# Schematics.net
KiCad netlist of a schematic drawn in Altium Designer
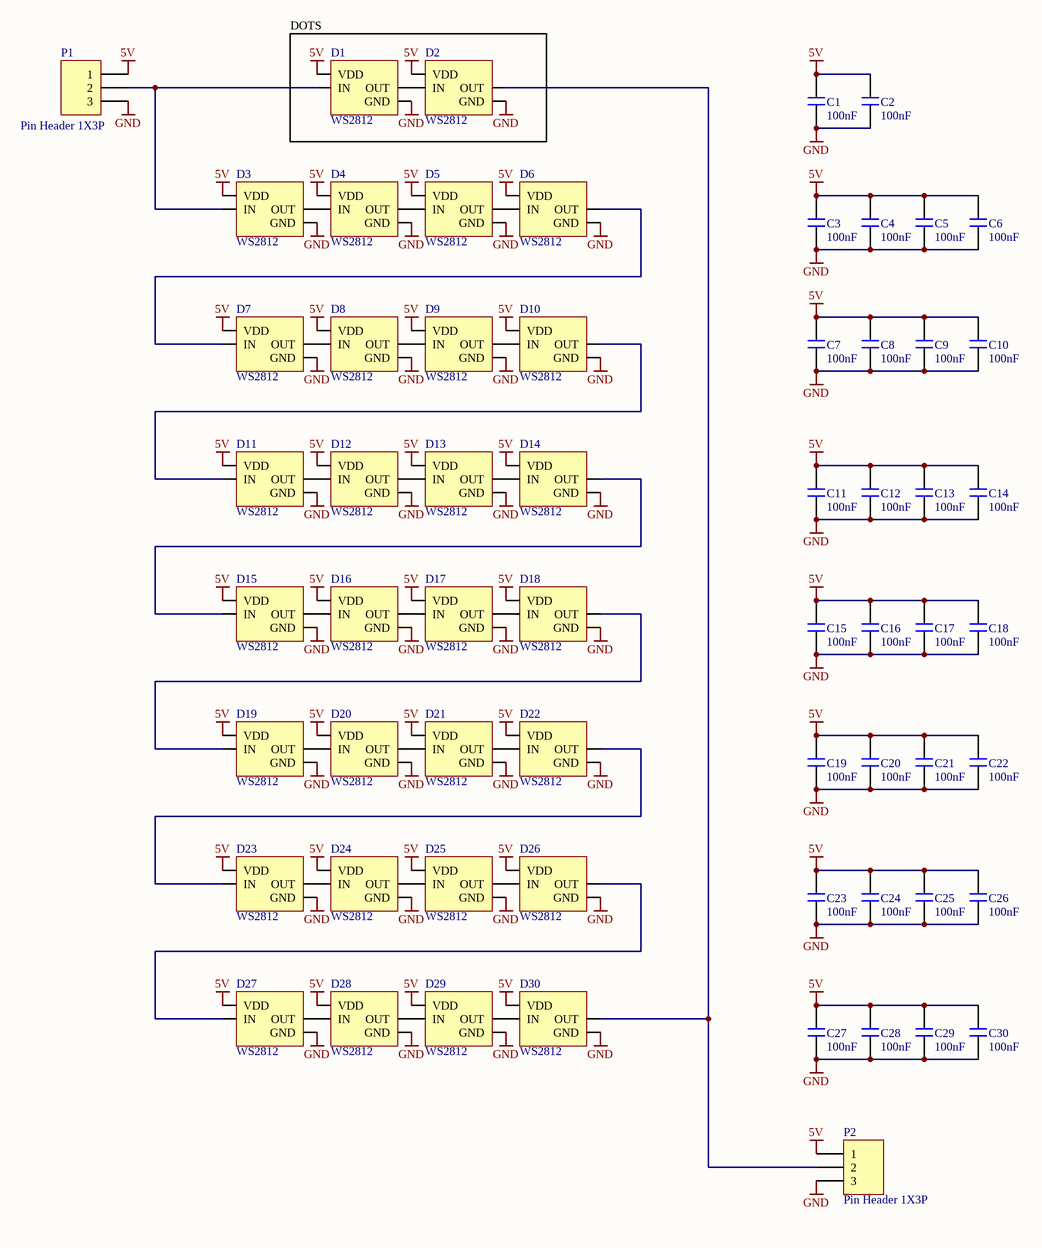
[diagram p0: Schematics.SchDoc]

(export (version "E")
  (design (tool "Eeschema 10.0.6"))
  (components
    (comp (ref "C1")
      (value "100nF")
      (footprint "EM-0805-C T1,25_SMD")
      (description "Capacitor")
      (fields (field (name "TOLERANCE") "+-5%"))
      (libsource (lib "Schematic") (part "Capacitor"))
    )
    (comp (ref "C2")
      (value "100nF")
      (footprint "EM-0805-C T1,25_SMD")
      (description "Capacitor")
      (fields (field (name "TOLERANCE") "+-5%"))
      (libsource (lib "Schematic") (part "Capacitor"))
    )
    (comp (ref "C3")
      (value "100nF")
      (footprint "EM-0805-C T1,25_SMD")
      (description "Capacitor")
      (fields (field (name "TOLERANCE") "+-5%"))
      (libsource (lib "Schematic") (part "Capacitor"))
    )
    (comp (ref "C4")
      (value "100nF")
      (footprint "EM-0805-C T1,25_SMD")
      (description "Capacitor")
      (fields (field (name "TOLERANCE") "+-5%"))
      (libsource (lib "Schematic") (part "Capacitor"))
    )
    (comp (ref "C5")
      (value "100nF")
      (footprint "EM-0805-C T1,25_SMD")
      (description "Capacitor")
      (fields (field (name "TOLERANCE") "+-5%"))
      (libsource (lib "Schematic") (part "Capacitor"))
    )
    (comp (ref "C6")
      (value "100nF")
      (footprint "EM-0805-C T1,25_SMD")
      (description "Capacitor")
      (fields (field (name "TOLERANCE") "+-5%"))
      (libsource (lib "Schematic") (part "Capacitor"))
    )
    (comp (ref "C7")
      (value "100nF")
      (footprint "EM-0805-C T1,25_SMD")
      (description "Capacitor")
      (fields (field (name "TOLERANCE") "+-5%"))
      (libsource (lib "Schematic") (part "Capacitor"))
    )
    (comp (ref "C8")
      (value "100nF")
      (footprint "EM-0805-C T1,25_SMD")
      (description "Capacitor")
      (fields (field (name "TOLERANCE") "+-5%"))
      (libsource (lib "Schematic") (part "Capacitor"))
    )
    (comp (ref "C9")
      (value "100nF")
      (footprint "EM-0805-C T1,25_SMD")
      (description "Capacitor")
      (fields (field (name "TOLERANCE") "+-5%"))
      (libsource (lib "Schematic") (part "Capacitor"))
    )
    (comp (ref "C10")
      (value "100nF")
      (footprint "EM-0805-C T1,25_SMD")
      (description "Capacitor")
      (fields (field (name "TOLERANCE") "+-5%"))
      (libsource (lib "Schematic") (part "Capacitor"))
    )
    (comp (ref "C11")
      (value "100nF")
      (footprint "EM-0805-C T1,25_SMD")
      (description "Capacitor")
      (fields (field (name "TOLERANCE") "+-5%"))
      (libsource (lib "Schematic") (part "Capacitor"))
    )
    (comp (ref "C12")
      (value "100nF")
      (footprint "EM-0805-C T1,25_SMD")
      (description "Capacitor")
      (fields (field (name "TOLERANCE") "+-5%"))
      (libsource (lib "Schematic") (part "Capacitor"))
    )
    (comp (ref "C13")
      (value "100nF")
      (footprint "EM-0805-C T1,25_SMD")
      (description "Capacitor")
      (fields (field (name "TOLERANCE") "+-5%"))
      (libsource (lib "Schematic") (part "Capacitor"))
    )
    (comp (ref "C14")
      (value "100nF")
      (footprint "EM-0805-C T1,25_SMD")
      (description "Capacitor")
      (fields (field (name "TOLERANCE") "+-5%"))
      (libsource (lib "Schematic") (part "Capacitor"))
    )
    (comp (ref "C15")
      (value "100nF")
      (footprint "EM-0805-C T1,25_SMD")
      (description "Capacitor")
      (fields (field (name "TOLERANCE") "+-5%"))
      (libsource (lib "Schematic") (part "Capacitor"))
    )
    (comp (ref "C16")
      (value "100nF")
      (footprint "EM-0805-C T1,25_SMD")
      (description "Capacitor")
      (fields (field (name "TOLERANCE") "+-5%"))
      (libsource (lib "Schematic") (part "Capacitor"))
    )
    (comp (ref "C17")
      (value "100nF")
      (footprint "EM-0805-C T1,25_SMD")
      (description "Capacitor")
      (fields (field (name "TOLERANCE") "+-5%"))
      (libsource (lib "Schematic") (part "Capacitor"))
    )
    (comp (ref "C18")
      (value "100nF")
      (footprint "EM-0805-C T1,25_SMD")
      (description "Capacitor")
      (fields (field (name "TOLERANCE") "+-5%"))
      (libsource (lib "Schematic") (part "Capacitor"))
    )
    (comp (ref "C19")
      (value "100nF")
      (footprint "EM-0805-C T1,25_SMD")
      (description "Capacitor")
      (fields (field (name "TOLERANCE") "+-5%"))
      (libsource (lib "Schematic") (part "Capacitor"))
    )
    (comp (ref "C20")
      (value "100nF")
      (footprint "EM-0805-C T1,25_SMD")
      (description "Capacitor")
      (fields (field (name "TOLERANCE") "+-5%"))
      (libsource (lib "Schematic") (part "Capacitor"))
    )
    (comp (ref "C21")
      (value "100nF")
      (footprint "EM-0805-C T1,25_SMD")
      (description "Capacitor")
      (fields (field (name "TOLERANCE") "+-5%"))
      (libsource (lib "Schematic") (part "Capacitor"))
    )
    (comp (ref "C22")
      (value "100nF")
      (footprint "EM-0805-C T1,25_SMD")
      (description "Capacitor")
      (fields (field (name "TOLERANCE") "+-5%"))
      (libsource (lib "Schematic") (part "Capacitor"))
    )
    (comp (ref "C23")
      (value "100nF")
      (footprint "EM-0805-C T1,25_SMD")
      (description "Capacitor")
      (fields (field (name "TOLERANCE") "+-5%"))
      (libsource (lib "Schematic") (part "Capacitor"))
    )
    (comp (ref "C24")
      (value "100nF")
      (footprint "EM-0805-C T1,25_SMD")
      (description "Capacitor")
      (fields (field (name "TOLERANCE") "+-5%"))
      (libsource (lib "Schematic") (part "Capacitor"))
    )
    (comp (ref "C25")
      (value "100nF")
      (footprint "EM-0805-C T1,25_SMD")
      (description "Capacitor")
      (fields (field (name "TOLERANCE") "+-5%"))
      (libsource (lib "Schematic") (part "Capacitor"))
    )
    (comp (ref "C26")
      (value "100nF")
      (footprint "EM-0805-C T1,25_SMD")
      (description "Capacitor")
      (fields (field (name "TOLERANCE") "+-5%"))
      (libsource (lib "Schematic") (part "Capacitor"))
    )
    (comp (ref "C27")
      (value "100nF")
      (footprint "EM-0805-C T1,25_SMD")
      (description "Capacitor")
      (fields (field (name "TOLERANCE") "+-5%"))
      (libsource (lib "Schematic") (part "Capacitor"))
    )
    (comp (ref "C28")
      (value "100nF")
      (footprint "EM-0805-C T1,25_SMD")
      (description "Capacitor")
      (fields (field (name "TOLERANCE") "+-5%"))
      (libsource (lib "Schematic") (part "Capacitor"))
    )
    (comp (ref "C29")
      (value "100nF")
      (footprint "EM-0805-C T1,25_SMD")
      (description "Capacitor")
      (fields (field (name "TOLERANCE") "+-5%"))
      (libsource (lib "Schematic") (part "Capacitor"))
    )
    (comp (ref "C30")
      (value "100nF")
      (footprint "EM-0805-C T1,25_SMD")
      (description "Capacitor")
      (fields (field (name "TOLERANCE") "+-5%"))
      (libsource (lib "Schematic") (part "Capacitor"))
    )
    (comp (ref "D1") (value "WS2812") (footprint "WS2812B") (libsource (lib "Schematic") (part "WS2812")))
    (comp (ref "D2") (value "WS2812") (footprint "WS2812B") (libsource (lib "Schematic") (part "WS2812")))
    (comp (ref "D3") (value "WS2812") (footprint "WS2812B") (libsource (lib "Schematic") (part "WS2812")))
    (comp (ref "D4") (value "WS2812") (footprint "WS2812B") (libsource (lib "Schematic") (part "WS2812")))
    (comp (ref "D5") (value "WS2812") (footprint "WS2812B") (libsource (lib "Schematic") (part "WS2812")))
    (comp (ref "D6") (value "WS2812") (footprint "WS2812B") (libsource (lib "Schematic") (part "WS2812")))
    (comp (ref "D7") (value "WS2812") (footprint "WS2812B") (libsource (lib "Schematic") (part "WS2812")))
    (comp (ref "D8") (value "WS2812") (footprint "WS2812B") (libsource (lib "Schematic") (part "WS2812")))
    (comp (ref "D9") (value "WS2812") (footprint "WS2812B") (libsource (lib "Schematic") (part "WS2812")))
    (comp (ref "D10") (value "WS2812") (footprint "WS2812B") (libsource (lib "Schematic") (part "WS2812")))
    (comp (ref "D11") (value "WS2812") (footprint "WS2812B") (libsource (lib "Schematic") (part "WS2812")))
    (comp (ref "D12") (value "WS2812") (footprint "WS2812B") (libsource (lib "Schematic") (part "WS2812")))
    (comp (ref "D13") (value "WS2812") (footprint "WS2812B") (libsource (lib "Schematic") (part "WS2812")))
    (comp (ref "D14") (value "WS2812") (footprint "WS2812B") (libsource (lib "Schematic") (part "WS2812")))
    (comp (ref "D15") (value "WS2812") (footprint "WS2812B") (libsource (lib "Schematic") (part "WS2812")))
    (comp (ref "D16") (value "WS2812") (footprint "WS2812B") (libsource (lib "Schematic") (part "WS2812")))
    (comp (ref "D17") (value "WS2812") (footprint "WS2812B") (libsource (lib "Schematic") (part "WS2812")))
    (comp (ref "D18") (value "WS2812") (footprint "WS2812B") (libsource (lib "Schematic") (part "WS2812")))
    (comp (ref "D19") (value "WS2812") (footprint "WS2812B") (libsource (lib "Schematic") (part "WS2812")))
    (comp (ref "D20") (value "WS2812") (footprint "WS2812B") (libsource (lib "Schematic") (part "WS2812")))
    (comp (ref "D21") (value "WS2812") (footprint "WS2812B") (libsource (lib "Schematic") (part "WS2812")))
    (comp (ref "D22") (value "WS2812") (footprint "WS2812B") (libsource (lib "Schematic") (part "WS2812")))
    (comp (ref "D23") (value "WS2812") (footprint "WS2812B") (libsource (lib "Schematic") (part "WS2812")))
    (comp (ref "D24") (value "WS2812") (footprint "WS2812B") (libsource (lib "Schematic") (part "WS2812")))
    (comp (ref "D25") (value "WS2812") (footprint "WS2812B") (libsource (lib "Schematic") (part "WS2812")))
    (comp (ref "D26") (value "WS2812") (footprint "WS2812B") (libsource (lib "Schematic") (part "WS2812")))
    (comp (ref "D27") (value "WS2812") (footprint "WS2812B") (libsource (lib "Schematic") (part "WS2812")))
    (comp (ref "D28") (value "WS2812") (footprint "WS2812B") (libsource (lib "Schematic") (part "WS2812")))
    (comp (ref "D29") (value "WS2812") (footprint "WS2812B") (libsource (lib "Schematic") (part "WS2812")))
    (comp (ref "D30") (value "WS2812") (footprint "WS2812B") (libsource (lib "Schematic") (part "WS2812")))
    (comp (ref "P1")
      (value "Pin Header 1X3P")
      (footprint "CON Header 1X3")
      (description "Header 3-Pin")
      (libsource (lib "Schematic") (part "Pin Header 3"))
    )
    (comp (ref "P2")
      (value "Pin Header 1X3P")
      (footprint "CON Header 1X3")
      (description "Header 3-Pin")
      (libsource (lib "") (part "Pin Header 3_1"))
    )
  )
  (nets
    (net (code "1") (name "5V") (class "Default")
      (node (ref "C1") (pin "2") (pinfunction "2_2") (pintype "passive"))
      (node (ref "C10") (pin "2") (pinfunction "2_2") (pintype "passive"))
      (node (ref "C11") (pin "2") (pinfunction "2_2") (pintype "passive"))
      (node (ref "C12") (pin "2") (pinfunction "2_2") (pintype "passive"))
      (node (ref "C13") (pin "2") (pinfunction "2_2") (pintype "passive"))
      (node (ref "C14") (pin "2") (pinfunction "2_2") (pintype "passive"))
      (node (ref "C15") (pin "2") (pinfunction "2_2") (pintype "passive"))
      (node (ref "C16") (pin "2") (pinfunction "2_2") (pintype "passive"))
      (node (ref "C17") (pin "2") (pinfunction "2_2") (pintype "passive"))
      (node (ref "C18") (pin "2") (pinfunction "2_2") (pintype "passive"))
      (node (ref "C19") (pin "2") (pinfunction "2_2") (pintype "passive"))
      (node (ref "C2") (pin "2") (pinfunction "2_2") (pintype "passive"))
      (node (ref "C20") (pin "2") (pinfunction "2_2") (pintype "passive"))
      (node (ref "C21") (pin "2") (pinfunction "2_2") (pintype "passive"))
      (node (ref "C22") (pin "2") (pinfunction "2_2") (pintype "passive"))
      (node (ref "C23") (pin "2") (pinfunction "2_2") (pintype "passive"))
      (node (ref "C24") (pin "2") (pinfunction "2_2") (pintype "passive"))
      (node (ref "C25") (pin "2") (pinfunction "2_2") (pintype "passive"))
      (node (ref "C26") (pin "2") (pinfunction "2_2") (pintype "passive"))
      (node (ref "C27") (pin "2") (pinfunction "2_2") (pintype "passive"))
      (node (ref "C28") (pin "2") (pinfunction "2_2") (pintype "passive"))
      (node (ref "C29") (pin "2") (pinfunction "2_2") (pintype "passive"))
      (node (ref "C3") (pin "2") (pinfunction "2_2") (pintype "passive"))
      (node (ref "C30") (pin "2") (pinfunction "2_2") (pintype "passive"))
      (node (ref "C4") (pin "2") (pinfunction "2_2") (pintype "passive"))
      (node (ref "C5") (pin "2") (pinfunction "2_2") (pintype "passive"))
      (node (ref "C6") (pin "2") (pinfunction "2_2") (pintype "passive"))
      (node (ref "C7") (pin "2") (pinfunction "2_2") (pintype "passive"))
      (node (ref "C8") (pin "2") (pinfunction "2_2") (pintype "passive"))
      (node (ref "C9") (pin "2") (pinfunction "2_2") (pintype "passive"))
      (node (ref "D1") (pin "1") (pinfunction "VDD_1") (pintype "passive"))
      (node (ref "D10") (pin "1") (pinfunction "VDD_1") (pintype "passive"))
      (node (ref "D11") (pin "1") (pinfunction "VDD_1") (pintype "passive"))
      (node (ref "D12") (pin "1") (pinfunction "VDD_1") (pintype "passive"))
      (node (ref "D13") (pin "1") (pinfunction "VDD_1") (pintype "passive"))
      (node (ref "D14") (pin "1") (pinfunction "VDD_1") (pintype "passive"))
      (node (ref "D15") (pin "1") (pinfunction "VDD_1") (pintype "passive"))
      (node (ref "D16") (pin "1") (pinfunction "VDD_1") (pintype "passive"))
      (node (ref "D17") (pin "1") (pinfunction "VDD_1") (pintype "passive"))
      (node (ref "D18") (pin "1") (pinfunction "VDD_1") (pintype "passive"))
      (node (ref "D19") (pin "1") (pinfunction "VDD_1") (pintype "passive"))
      (node (ref "D2") (pin "1") (pinfunction "VDD_1") (pintype "passive"))
      (node (ref "D20") (pin "1") (pinfunction "VDD_1") (pintype "passive"))
      (node (ref "D21") (pin "1") (pinfunction "VDD_1") (pintype "passive"))
      (node (ref "D22") (pin "1") (pinfunction "VDD_1") (pintype "passive"))
      (node (ref "D23") (pin "1") (pinfunction "VDD_1") (pintype "passive"))
      (node (ref "D24") (pin "1") (pinfunction "VDD_1") (pintype "passive"))
      (node (ref "D25") (pin "1") (pinfunction "VDD_1") (pintype "passive"))
      (node (ref "D26") (pin "1") (pinfunction "VDD_1") (pintype "passive"))
      (node (ref "D27") (pin "1") (pinfunction "VDD_1") (pintype "passive"))
      (node (ref "D28") (pin "1") (pinfunction "VDD_1") (pintype "passive"))
      (node (ref "D29") (pin "1") (pinfunction "VDD_1") (pintype "passive"))
      (node (ref "D3") (pin "1") (pinfunction "VDD_1") (pintype "passive"))
      (node (ref "D30") (pin "1") (pinfunction "VDD_1") (pintype "passive"))
      (node (ref "D4") (pin "1") (pinfunction "VDD_1") (pintype "passive"))
      (node (ref "D5") (pin "1") (pinfunction "VDD_1") (pintype "passive"))
      (node (ref "D6") (pin "1") (pinfunction "VDD_1") (pintype "passive"))
      (node (ref "D7") (pin "1") (pinfunction "VDD_1") (pintype "passive"))
      (node (ref "D8") (pin "1") (pinfunction "VDD_1") (pintype "passive"))
      (node (ref "D9") (pin "1") (pinfunction "VDD_1") (pintype "passive"))
      (node (ref "P1") (pin "1") (pinfunction "1_1") (pintype "passive"))
      (node (ref "P2") (pin "1") (pinfunction "1_1") (pintype "passive"))
    )
    (net (code "2") (name "GND") (class "Default")
      (node (ref "C1") (pin "1") (pinfunction "1_1") (pintype "passive"))
      (node (ref "C10") (pin "1") (pinfunction "1_1") (pintype "passive"))
      (node (ref "C11") (pin "1") (pinfunction "1_1") (pintype "passive"))
      (node (ref "C12") (pin "1") (pinfunction "1_1") (pintype "passive"))
      (node (ref "C13") (pin "1") (pinfunction "1_1") (pintype "passive"))
      (node (ref "C14") (pin "1") (pinfunction "1_1") (pintype "passive"))
      (node (ref "C15") (pin "1") (pinfunction "1_1") (pintype "passive"))
      (node (ref "C16") (pin "1") (pinfunction "1_1") (pintype "passive"))
      (node (ref "C17") (pin "1") (pinfunction "1_1") (pintype "passive"))
      (node (ref "C18") (pin "1") (pinfunction "1_1") (pintype "passive"))
      (node (ref "C19") (pin "1") (pinfunction "1_1") (pintype "passive"))
      (node (ref "C2") (pin "1") (pinfunction "1_1") (pintype "passive"))
      (node (ref "C20") (pin "1") (pinfunction "1_1") (pintype "passive"))
      (node (ref "C21") (pin "1") (pinfunction "1_1") (pintype "passive"))
      (node (ref "C22") (pin "1") (pinfunction "1_1") (pintype "passive"))
      (node (ref "C23") (pin "1") (pinfunction "1_1") (pintype "passive"))
      (node (ref "C24") (pin "1") (pinfunction "1_1") (pintype "passive"))
      (node (ref "C25") (pin "1") (pinfunction "1_1") (pintype "passive"))
      (node (ref "C26") (pin "1") (pinfunction "1_1") (pintype "passive"))
      (node (ref "C27") (pin "1") (pinfunction "1_1") (pintype "passive"))
      (node (ref "C28") (pin "1") (pinfunction "1_1") (pintype "passive"))
      (node (ref "C29") (pin "1") (pinfunction "1_1") (pintype "passive"))
      (node (ref "C3") (pin "1") (pinfunction "1_1") (pintype "passive"))
      (node (ref "C30") (pin "1") (pinfunction "1_1") (pintype "passive"))
      (node (ref "C4") (pin "1") (pinfunction "1_1") (pintype "passive"))
      (node (ref "C5") (pin "1") (pinfunction "1_1") (pintype "passive"))
      (node (ref "C6") (pin "1") (pinfunction "1_1") (pintype "passive"))
      (node (ref "C7") (pin "1") (pinfunction "1_1") (pintype "passive"))
      (node (ref "C8") (pin "1") (pinfunction "1_1") (pintype "passive"))
      (node (ref "C9") (pin "1") (pinfunction "1_1") (pintype "passive"))
      (node (ref "D1") (pin "3") (pinfunction "GND_3") (pintype "passive"))
      (node (ref "D10") (pin "3") (pinfunction "GND_3") (pintype "passive"))
      (node (ref "D11") (pin "3") (pinfunction "GND_3") (pintype "passive"))
      (node (ref "D12") (pin "3") (pinfunction "GND_3") (pintype "passive"))
      (node (ref "D13") (pin "3") (pinfunction "GND_3") (pintype "passive"))
      (node (ref "D14") (pin "3") (pinfunction "GND_3") (pintype "passive"))
      (node (ref "D15") (pin "3") (pinfunction "GND_3") (pintype "passive"))
      (node (ref "D16") (pin "3") (pinfunction "GND_3") (pintype "passive"))
      (node (ref "D17") (pin "3") (pinfunction "GND_3") (pintype "passive"))
      (node (ref "D18") (pin "3") (pinfunction "GND_3") (pintype "passive"))
      (node (ref "D19") (pin "3") (pinfunction "GND_3") (pintype "passive"))
      (node (ref "D2") (pin "3") (pinfunction "GND_3") (pintype "passive"))
      (node (ref "D20") (pin "3") (pinfunction "GND_3") (pintype "passive"))
      (node (ref "D21") (pin "3") (pinfunction "GND_3") (pintype "passive"))
      (node (ref "D22") (pin "3") (pinfunction "GND_3") (pintype "passive"))
      (node (ref "D23") (pin "3") (pinfunction "GND_3") (pintype "passive"))
      (node (ref "D24") (pin "3") (pinfunction "GND_3") (pintype "passive"))
      (node (ref "D25") (pin "3") (pinfunction "GND_3") (pintype "passive"))
      (node (ref "D26") (pin "3") (pinfunction "GND_3") (pintype "passive"))
      (node (ref "D27") (pin "3") (pinfunction "GND_3") (pintype "passive"))
      (node (ref "D28") (pin "3") (pinfunction "GND_3") (pintype "passive"))
      (node (ref "D29") (pin "3") (pinfunction "GND_3") (pintype "passive"))
      (node (ref "D3") (pin "3") (pinfunction "GND_3") (pintype "passive"))
      (node (ref "D30") (pin "3") (pinfunction "GND_3") (pintype "passive"))
      (node (ref "D4") (pin "3") (pinfunction "GND_3") (pintype "passive"))
      (node (ref "D5") (pin "3") (pinfunction "GND_3") (pintype "passive"))
      (node (ref "D6") (pin "3") (pinfunction "GND_3") (pintype "passive"))
      (node (ref "D7") (pin "3") (pinfunction "GND_3") (pintype "passive"))
      (node (ref "D8") (pin "3") (pinfunction "GND_3") (pintype "passive"))
      (node (ref "D9") (pin "3") (pinfunction "GND_3") (pintype "passive"))
      (node (ref "P1") (pin "3") (pinfunction "3_3") (pintype "passive"))
      (node (ref "P2") (pin "3") (pinfunction "3_3") (pintype "passive"))
    )
    (net (code "3") (name "Net-(D1-IN)") (class "Default")
      (node (ref "D1") (pin "4") (pinfunction "IN_4") (pintype "passive"))
      (node (ref "D3") (pin "4") (pinfunction "IN_4") (pintype "passive"))
      (node (ref "P1") (pin "2") (pinfunction "2_2") (pintype "passive"))
    )
    (net (code "4") (name "Net-(D1-OUT)") (class "Default")
      (node (ref "D1") (pin "2") (pinfunction "OUT_2") (pintype "passive"))
      (node (ref "D2") (pin "4") (pinfunction "IN_4") (pintype "passive"))
    )
    (net (code "5") (name "Net-(D2-OUT)") (class "Default")
      (node (ref "D2") (pin "2") (pinfunction "OUT_2") (pintype "passive"))
      (node (ref "D30") (pin "2") (pinfunction "OUT_2") (pintype "passive"))
      (node (ref "P2") (pin "2") (pinfunction "2_2") (pintype "passive"))
    )
    (net (code "6") (name "Net-(D3-OUT)") (class "Default")
      (node (ref "D3") (pin "2") (pinfunction "OUT_2") (pintype "passive"))
      (node (ref "D4") (pin "4") (pinfunction "IN_4") (pintype "passive"))
    )
    (net (code "7") (name "Net-(D4-OUT)") (class "Default")
      (node (ref "D4") (pin "2") (pinfunction "OUT_2") (pintype "passive"))
      (node (ref "D5") (pin "4") (pinfunction "IN_4") (pintype "passive"))
    )
    (net (code "8") (name "Net-(D5-OUT)") (class "Default")
      (node (ref "D5") (pin "2") (pinfunction "OUT_2") (pintype "passive"))
      (node (ref "D6") (pin "4") (pinfunction "IN_4") (pintype "passive"))
    )
    (net (code "9") (name "Net-(D6-OUT)") (class "Default")
      (node (ref "D6") (pin "2") (pinfunction "OUT_2") (pintype "passive"))
      (node (ref "D7") (pin "4") (pinfunction "IN_4") (pintype "passive"))
    )
    (net (code "10") (name "Net-(D7-OUT)") (class "Default")
      (node (ref "D7") (pin "2") (pinfunction "OUT_2") (pintype "passive"))
      (node (ref "D8") (pin "4") (pinfunction "IN_4") (pintype "passive"))
    )
    (net (code "11") (name "Net-(D8-OUT)") (class "Default")
      (node (ref "D8") (pin "2") (pinfunction "OUT_2") (pintype "passive"))
      (node (ref "D9") (pin "4") (pinfunction "IN_4") (pintype "passive"))
    )
    (net (code "12") (name "Net-(D10-IN)") (class "Default")
      (node (ref "D10") (pin "4") (pinfunction "IN_4") (pintype "passive"))
      (node (ref "D9") (pin "2") (pinfunction "OUT_2") (pintype "passive"))
    )
    (net (code "13") (name "Net-(D10-OUT)") (class "Default")
      (node (ref "D10") (pin "2") (pinfunction "OUT_2") (pintype "passive"))
      (node (ref "D11") (pin "4") (pinfunction "IN_4") (pintype "passive"))
    )
    (net (code "14") (name "Net-(D11-OUT)") (class "Default")
      (node (ref "D11") (pin "2") (pinfunction "OUT_2") (pintype "passive"))
      (node (ref "D12") (pin "4") (pinfunction "IN_4") (pintype "passive"))
    )
    (net (code "15") (name "Net-(D12-OUT)") (class "Default")
      (node (ref "D12") (pin "2") (pinfunction "OUT_2") (pintype "passive"))
      (node (ref "D13") (pin "4") (pinfunction "IN_4") (pintype "passive"))
    )
    (net (code "16") (name "Net-(D13-OUT)") (class "Default")
      (node (ref "D13") (pin "2") (pinfunction "OUT_2") (pintype "passive"))
      (node (ref "D14") (pin "4") (pinfunction "IN_4") (pintype "passive"))
    )
    (net (code "17") (name "Net-(D14-OUT)") (class "Default")
      (node (ref "D14") (pin "2") (pinfunction "OUT_2") (pintype "passive"))
      (node (ref "D15") (pin "4") (pinfunction "IN_4") (pintype "passive"))
    )
    (net (code "18") (name "Net-(D15-OUT)") (class "Default")
      (node (ref "D15") (pin "2") (pinfunction "OUT_2") (pintype "passive"))
      (node (ref "D16") (pin "4") (pinfunction "IN_4") (pintype "passive"))
    )
    (net (code "19") (name "Net-(D16-OUT)") (class "Default")
      (node (ref "D16") (pin "2") (pinfunction "OUT_2") (pintype "passive"))
      (node (ref "D17") (pin "4") (pinfunction "IN_4") (pintype "passive"))
    )
    (net (code "20") (name "Net-(D17-OUT)") (class "Default")
      (node (ref "D17") (pin "2") (pinfunction "OUT_2") (pintype "passive"))
      (node (ref "D18") (pin "4") (pinfunction "IN_4") (pintype "passive"))
    )
    (net (code "21") (name "Net-(D18-OUT)") (class "Default")
      (node (ref "D18") (pin "2") (pinfunction "OUT_2") (pintype "passive"))
      (node (ref "D19") (pin "4") (pinfunction "IN_4") (pintype "passive"))
    )
    (net (code "22") (name "Net-(D19-OUT)") (class "Default")
      (node (ref "D19") (pin "2") (pinfunction "OUT_2") (pintype "passive"))
      (node (ref "D20") (pin "4") (pinfunction "IN_4") (pintype "passive"))
    )
    (net (code "23") (name "Net-(D20-OUT)") (class "Default")
      (node (ref "D20") (pin "2") (pinfunction "OUT_2") (pintype "passive"))
      (node (ref "D21") (pin "4") (pinfunction "IN_4") (pintype "passive"))
    )
    (net (code "24") (name "Net-(D21-OUT)") (class "Default")
      (node (ref "D21") (pin "2") (pinfunction "OUT_2") (pintype "passive"))
      (node (ref "D22") (pin "4") (pinfunction "IN_4") (pintype "passive"))
    )
    (net (code "25") (name "Net-(D22-OUT)") (class "Default")
      (node (ref "D22") (pin "2") (pinfunction "OUT_2") (pintype "passive"))
      (node (ref "D23") (pin "4") (pinfunction "IN_4") (pintype "passive"))
    )
    (net (code "26") (name "Net-(D23-OUT)") (class "Default")
      (node (ref "D23") (pin "2") (pinfunction "OUT_2") (pintype "passive"))
      (node (ref "D24") (pin "4") (pinfunction "IN_4") (pintype "passive"))
    )
    (net (code "27") (name "Net-(D24-OUT)") (class "Default")
      (node (ref "D24") (pin "2") (pinfunction "OUT_2") (pintype "passive"))
      (node (ref "D25") (pin "4") (pinfunction "IN_4") (pintype "passive"))
    )
    (net (code "28") (name "Net-(D25-OUT)") (class "Default")
      (node (ref "D25") (pin "2") (pinfunction "OUT_2") (pintype "passive"))
      (node (ref "D26") (pin "4") (pinfunction "IN_4") (pintype "passive"))
    )
    (net (code "29") (name "Net-(D26-OUT)") (class "Default")
      (node (ref "D26") (pin "2") (pinfunction "OUT_2") (pintype "passive"))
      (node (ref "D27") (pin "4") (pinfunction "IN_4") (pintype "passive"))
    )
    (net (code "30") (name "Net-(D27-OUT)") (class "Default")
      (node (ref "D27") (pin "2") (pinfunction "OUT_2") (pintype "passive"))
      (node (ref "D28") (pin "4") (pinfunction "IN_4") (pintype "passive"))
    )
    (net (code "31") (name "Net-(D28-OUT)") (class "Default")
      (node (ref "D28") (pin "2") (pinfunction "OUT_2") (pintype "passive"))
      (node (ref "D29") (pin "4") (pinfunction "IN_4") (pintype "passive"))
    )
    (net (code "32") (name "Net-(D29-OUT)") (class "Default")
      (node (ref "D29") (pin "2") (pinfunction "OUT_2") (pintype "passive"))
      (node (ref "D30") (pin "4") (pinfunction "IN_4") (pintype "passive"))
    )
  )
)
